# Line_trigger.net
KiCad netlist of a schematic drawn in Altium Designer
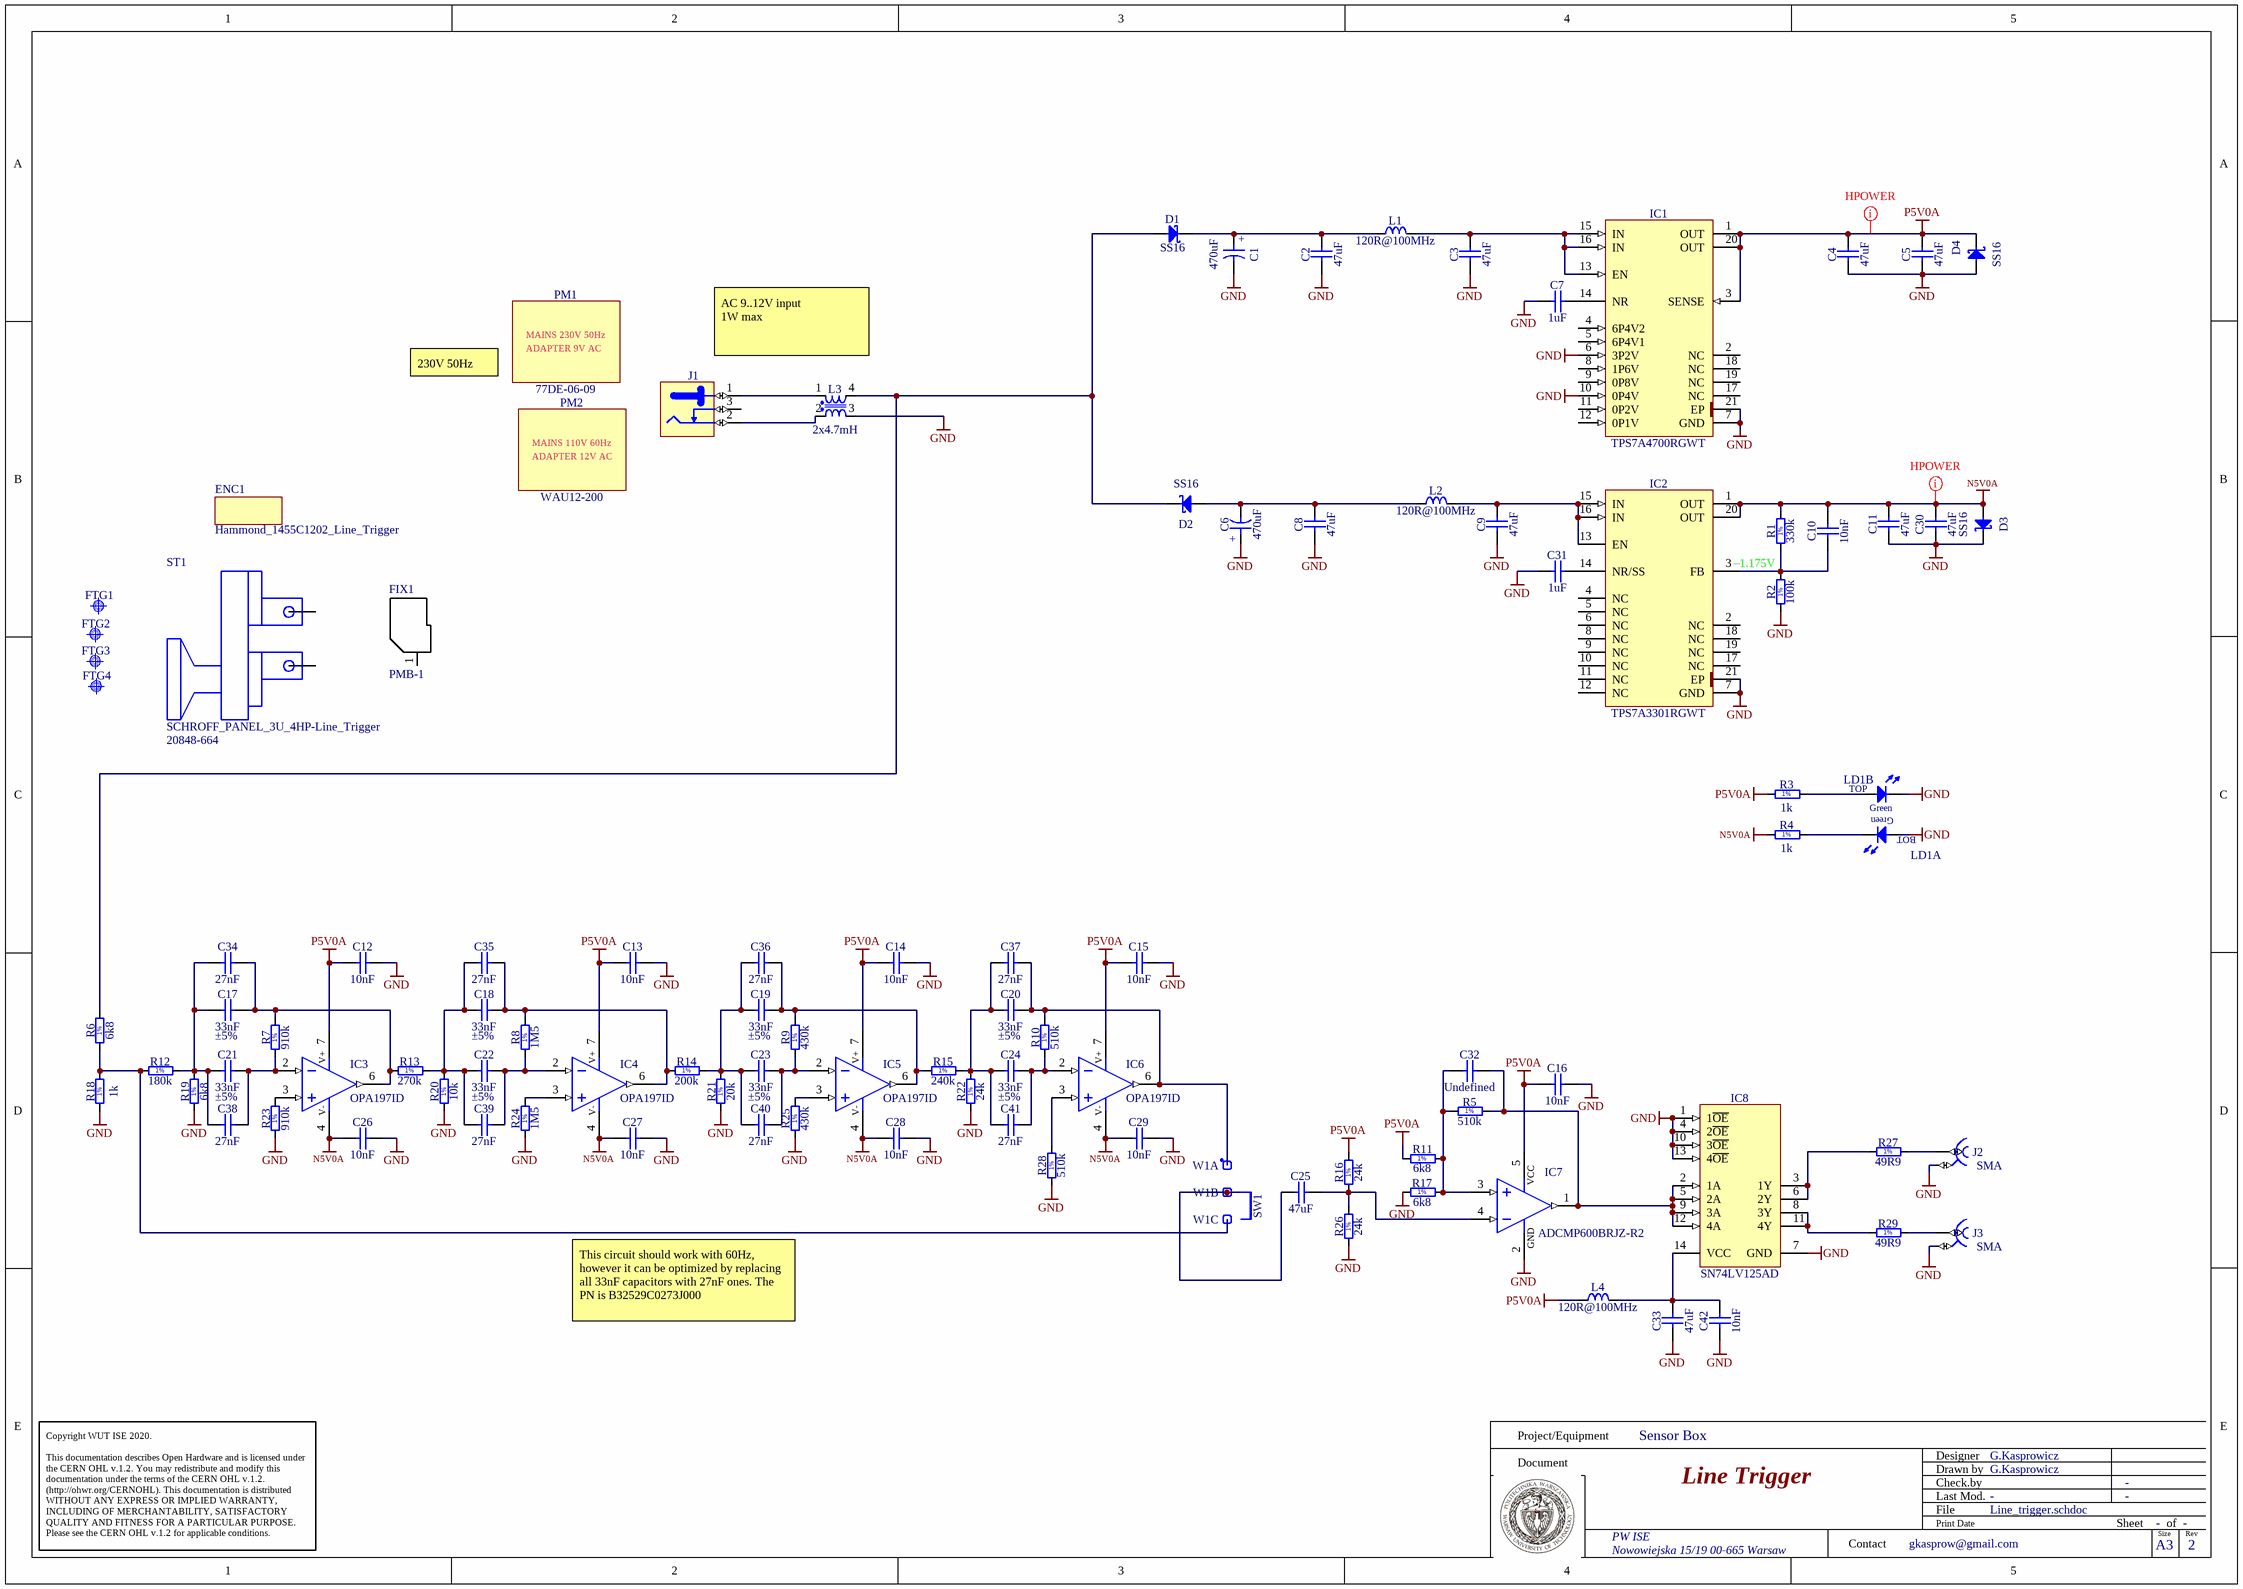
[diagram p0: Line_trigger.schdoc]

(export (version "E")
  (design (tool "Eeschema 10.0.6"))
  (components
    (comp (ref "C1")
      (value "470uF")
      (footprint "CAPAE1030X1020N")
      (description "Polarised capacitor")
      (fields (field (name "PART NUMBER") "CAE1030-1020_470UF_25V_20%") (field (name "VOLTAGE") "25V"))
      (libsource (lib "Capacitors") (part "Capacitor - polarized"))
    )
    (comp (ref "C2")
      (value "47uF")
      (footprint "CAPC3216X180N")
      (description "Non-polarised capacitor")
      (fields (field (name "PART NUMBER") "CC1206_47UF_25V_20%_X5R") (field (name "VOLTAGE") "25V"))
      (libsource (lib "Capacitors") (part "Capacitor - non polarized"))
    )
    (comp (ref "C3")
      (value "47uF")
      (footprint "CAPC3216X180N")
      (description "Non-polarised capacitor")
      (fields (field (name "PART NUMBER") "CC1206_47UF_25V_20%_X5R") (field (name "VOLTAGE") "25V"))
      (libsource (lib "Capacitors") (part "Capacitor - non polarized"))
    )
    (comp (ref "C4")
      (value "47uF")
      (footprint "CAPC3216X180N")
      (description "Non-polarised capacitor")
      (fields (field (name "PART NUMBER") "CC1206_47UF_25V_20%_X5R") (field (name "VOLTAGE") "25V"))
      (libsource (lib "Capacitors") (part "Capacitor - non polarized"))
    )
    (comp (ref "C5")
      (value "47uF")
      (footprint "CAPC3216X180N")
      (description "Non-polarised capacitor")
      (fields (field (name "PART NUMBER") "CC1206_47UF_25V_20%_X5R") (field (name "VOLTAGE") "25V"))
      (libsource (lib "Capacitors") (part "Capacitor - non polarized"))
    )
    (comp (ref "C6")
      (value "470uF")
      (footprint "CAPAE1030X1020N")
      (description "Polarised capacitor")
      (fields (field (name "PART NUMBER") "CAE1030-1020_470UF_25V_20%") (field (name "VOLTAGE") "25V"))
      (libsource (lib "Capacitors") (part "Capacitor - polarized"))
    )
    (comp (ref "C7")
      (value "1uF")
      (footprint "CAPC1608X87N")
      (description "Non-polarised capacitor")
      (fields (field (name "PART NUMBER") "CC0603_1UF_25V_10%_X7R") (field (name "VOLTAGE") "25V"))
      (libsource (lib "Capacitors") (part "Capacitor - non polarized"))
    )
    (comp (ref "C8")
      (value "47uF")
      (footprint "CAPC3216X180N")
      (description "Non-polarised capacitor")
      (fields (field (name "PART NUMBER") "CC1206_47UF_25V_20%_X5R") (field (name "VOLTAGE") "25V"))
      (libsource (lib "Capacitors") (part "Capacitor - non polarized"))
    )
    (comp (ref "C9")
      (value "47uF")
      (footprint "CAPC3216X180N")
      (description "Non-polarised capacitor")
      (fields (field (name "PART NUMBER") "CC1206_47UF_25V_20%_X5R") (field (name "VOLTAGE") "25V"))
      (libsource (lib "Capacitors") (part "Capacitor - non polarized"))
    )
    (comp (ref "C10")
      (value "10nF")
      (footprint "CAPC1608X87N")
      (description "Non-polarised capacitor")
      (fields (field (name "PART NUMBER") "CC0603_10NF_50V_10%_X7R") (field (name "VOLTAGE") "50V"))
      (libsource (lib "Capacitors") (part "Capacitor - non polarized"))
    )
    (comp (ref "C11")
      (value "47uF")
      (footprint "CAPC3216X180N")
      (description "Non-polarised capacitor")
      (fields (field (name "PART NUMBER") "CC1206_47UF_25V_20%_X5R") (field (name "VOLTAGE") "25V"))
      (libsource (lib "Capacitors") (part "Capacitor - non polarized"))
    )
    (comp (ref "C12")
      (value "10nF")
      (footprint "CAPC1608X87N")
      (description "Non-polarised capacitor")
      (fields (field (name "PART NUMBER") "CC0603_10NF_50V_10%_X7R") (field (name "VOLTAGE") "50V"))
      (libsource (lib "Capacitors") (part "Capacitor - non polarized"))
    )
    (comp (ref "C13")
      (value "10nF")
      (footprint "CAPC1608X87N")
      (description "Non-polarised capacitor")
      (fields (field (name "PART NUMBER") "CC0603_10NF_50V_10%_X7R") (field (name "VOLTAGE") "50V"))
      (libsource (lib "Capacitors") (part "Capacitor - non polarized"))
    )
    (comp (ref "C14")
      (value "10nF")
      (footprint "CAPC1608X87N")
      (description "Non-polarised capacitor")
      (fields (field (name "PART NUMBER") "CC0603_10NF_50V_10%_X7R") (field (name "VOLTAGE") "50V"))
      (libsource (lib "Capacitors") (part "Capacitor - non polarized"))
    )
    (comp (ref "C15")
      (value "10nF")
      (footprint "CAPC1608X87N")
      (description "Non-polarised capacitor")
      (fields (field (name "PART NUMBER") "CC0603_10NF_50V_10%_X7R") (field (name "VOLTAGE") "50V"))
      (libsource (lib "Capacitors") (part "Capacitor - non polarized"))
    )
    (comp (ref "C16")
      (value "10nF")
      (footprint "CAPC1608X87N")
      (description "Non-polarised capacitor")
      (fields (field (name "PART NUMBER") "CC0603_10NF_50V_10%_X7R") (field (name "VOLTAGE") "50V"))
      (libsource (lib "Capacitors") (part "Capacitor - non polarized"))
    )
    (comp (ref "C17")
      (value "33nF")
      (footprint "CAPR500-250X720X650")
      (description "Non-polarised capacitor")
      (fields
        (field (name "PART NUMBER") "CPER_33NF_63V_10%_500-250X720X650")
        (field (name "VOLTAGE") "63VDC/40VAC")
        (field (name "TOLERANCE") "±5%")
      )
      (libsource (lib "Passives_RC") (part "CAP_MKT_33n_63V"))
    )
    (comp (ref "C18")
      (value "33nF")
      (footprint "CAPR500-250X720X650")
      (description "Non-polarised capacitor")
      (fields
        (field (name "PART NUMBER") "CPER_33NF_63V_10%_500-250X720X650")
        (field (name "VOLTAGE") "63VDC/40VAC")
        (field (name "TOLERANCE") "±5%")
      )
      (libsource (lib "Passives_RC") (part "CAP_MKT_33n_63V"))
    )
    (comp (ref "C19")
      (value "33nF")
      (footprint "CAPR500-250X720X650")
      (description "Non-polarised capacitor")
      (fields
        (field (name "PART NUMBER") "CPER_33NF_63V_10%_500-250X720X650")
        (field (name "VOLTAGE") "63VDC/40VAC")
        (field (name "TOLERANCE") "±5%")
      )
      (libsource (lib "Passives_RC") (part "CAP_MKT_33n_63V"))
    )
    (comp (ref "C20")
      (value "33nF")
      (footprint "CAPR500-250X720X650")
      (description "Non-polarised capacitor")
      (fields
        (field (name "PART NUMBER") "CPER_33NF_63V_10%_500-250X720X650")
        (field (name "VOLTAGE") "63VDC/40VAC")
        (field (name "TOLERANCE") "±5%")
      )
      (libsource (lib "Passives_RC") (part "CAP_MKT_33n_63V"))
    )
    (comp (ref "C21")
      (value "33nF")
      (footprint "CAPR500-250X720X650")
      (description "Non-polarised capacitor")
      (fields
        (field (name "PART NUMBER") "CPER_33NF_63V_10%_500-250X720X650")
        (field (name "VOLTAGE") "63VDC/40VAC")
        (field (name "TOLERANCE") "±5%")
      )
      (libsource (lib "Passives_RC") (part "CAP_MKT_33n_63V"))
    )
    (comp (ref "C22")
      (value "33nF")
      (footprint "CAPR500-250X720X650")
      (description "Non-polarised capacitor")
      (fields
        (field (name "PART NUMBER") "CPER_33NF_63V_10%_500-250X720X650")
        (field (name "VOLTAGE") "63VDC/40VAC")
        (field (name "TOLERANCE") "±5%")
      )
      (libsource (lib "Passives_RC") (part "CAP_MKT_33n_63V"))
    )
    (comp (ref "C23")
      (value "33nF")
      (footprint "CAPR500-250X720X650")
      (description "Non-polarised capacitor")
      (fields
        (field (name "PART NUMBER") "CPER_33NF_63V_10%_500-250X720X650")
        (field (name "VOLTAGE") "63VDC/40VAC")
        (field (name "TOLERANCE") "±5%")
      )
      (libsource (lib "Passives_RC") (part "CAP_MKT_33n_63V"))
    )
    (comp (ref "C24")
      (value "33nF")
      (footprint "CAPR500-250X720X650")
      (description "Non-polarised capacitor")
      (fields
        (field (name "PART NUMBER") "CPER_33NF_63V_10%_500-250X720X650")
        (field (name "VOLTAGE") "63VDC/40VAC")
        (field (name "TOLERANCE") "±5%")
      )
      (libsource (lib "Passives_RC") (part "CAP_MKT_33n_63V"))
    )
    (comp (ref "C25")
      (value "47uF")
      (footprint "CAPC3216X180N")
      (description "Non-polarised capacitor")
      (fields (field (name "PART NUMBER") "CC1206_47UF_25V_20%_X5R") (field (name "VOLTAGE") "25V"))
      (libsource (lib "Capacitors") (part "Capacitor - non polarized"))
    )
    (comp (ref "C26")
      (value "10nF")
      (footprint "CAPC1608X87N")
      (description "Non-polarised capacitor")
      (fields (field (name "PART NUMBER") "CC0603_10NF_50V_10%_X7R") (field (name "VOLTAGE") "50V"))
      (libsource (lib "Capacitors") (part "Capacitor - non polarized"))
    )
    (comp (ref "C27")
      (value "10nF")
      (footprint "CAPC1608X87N")
      (description "Non-polarised capacitor")
      (fields (field (name "PART NUMBER") "CC0603_10NF_50V_10%_X7R") (field (name "VOLTAGE") "50V"))
      (libsource (lib "Capacitors") (part "Capacitor - non polarized"))
    )
    (comp (ref "C28")
      (value "10nF")
      (footprint "CAPC1608X87N")
      (description "Non-polarised capacitor")
      (fields (field (name "PART NUMBER") "CC0603_10NF_50V_10%_X7R") (field (name "VOLTAGE") "50V"))
      (libsource (lib "Capacitors") (part "Capacitor - non polarized"))
    )
    (comp (ref "C29")
      (value "10nF")
      (footprint "CAPC1608X87N")
      (description "Non-polarised capacitor")
      (fields (field (name "PART NUMBER") "CC0603_10NF_50V_10%_X7R") (field (name "VOLTAGE") "50V"))
      (libsource (lib "Capacitors") (part "Capacitor - non polarized"))
    )
    (comp (ref "C30")
      (value "47uF")
      (footprint "CAPC3216X180N")
      (description "Non-polarised capacitor")
      (fields (field (name "PART NUMBER") "CC1206_47UF_25V_20%_X5R") (field (name "VOLTAGE") "25V"))
      (libsource (lib "Capacitors") (part "Capacitor - non polarized"))
    )
    (comp (ref "C31")
      (value "1uF")
      (footprint "CAPC1608X87N")
      (description "Non-polarised capacitor")
      (fields (field (name "PART NUMBER") "CC0603_1UF_25V_10%_X7R") (field (name "VOLTAGE") "25V"))
      (libsource (lib "Capacitors") (part "Capacitor - non polarized"))
    )
    (comp (ref "C32")
      (value "Undefined")
      (footprint "CAPC1608X90N")
      (description "Non-polarised capacitor")
      (fields (field (name "PART NUMBER") "CC0603_NO-VALUE"))
      (libsource (lib "Capacitors") (part "Capacitor - non polarized"))
    )
    (comp (ref "C33")
      (value "47uF")
      (footprint "CAPC3216X180N")
      (description "Non-polarised capacitor")
      (fields (field (name "PART NUMBER") "CC1206_47UF_25V_20%_X5R") (field (name "VOLTAGE") "25V"))
      (libsource (lib "Capacitors") (part "Capacitor - non polarized"))
    )
    (comp (ref "C34")
      (value "27nF")
      (footprint "CAPR500-250X720X650")
      (description "Non-polarised capacitor")
      (fields
        (field (name "PART NUMBER") "CPER_27NF_63V_10%_500-250X720X650")
        (field (name "VOLTAGE") "63VDC/40VAC")
      )
      (libsource (lib "Passives_RC") (part "CAP_MKT_27n_63V"))
    )
    (comp (ref "C35")
      (value "27nF")
      (footprint "CAPR500-250X720X650")
      (description "Non-polarised capacitor")
      (fields
        (field (name "PART NUMBER") "CPER_27NF_63V_10%_500-250X720X650")
        (field (name "VOLTAGE") "63VDC/40VAC")
      )
      (libsource (lib "Passives_RC") (part "CAP_MKT_27n_63V"))
    )
    (comp (ref "C36")
      (value "27nF")
      (footprint "CAPR500-250X720X650")
      (description "Non-polarised capacitor")
      (fields
        (field (name "PART NUMBER") "CPER_27NF_63V_10%_500-250X720X650")
        (field (name "VOLTAGE") "63VDC/40VAC")
      )
      (libsource (lib "Passives_RC") (part "CAP_MKT_27n_63V"))
    )
    (comp (ref "C37")
      (value "27nF")
      (footprint "CAPR500-250X720X650")
      (description "Non-polarised capacitor")
      (fields
        (field (name "PART NUMBER") "CPER_27NF_63V_10%_500-250X720X650")
        (field (name "VOLTAGE") "63VDC/40VAC")
      )
      (libsource (lib "Passives_RC") (part "CAP_MKT_27n_63V"))
    )
    (comp (ref "C38")
      (value "27nF")
      (footprint "CAPR500-250X720X650")
      (description "Non-polarised capacitor")
      (fields
        (field (name "PART NUMBER") "CPER_27NF_63V_10%_500-250X720X650")
        (field (name "VOLTAGE") "63VDC/40VAC")
      )
      (libsource (lib "Passives_RC") (part "CAP_MKT_27n_63V"))
    )
    (comp (ref "C39")
      (value "27nF")
      (footprint "CAPR500-250X720X650")
      (description "Non-polarised capacitor")
      (fields
        (field (name "PART NUMBER") "CPER_27NF_63V_10%_500-250X720X650")
        (field (name "VOLTAGE") "63VDC/40VAC")
      )
      (libsource (lib "Passives_RC") (part "CAP_MKT_27n_63V"))
    )
    (comp (ref "C40")
      (value "27nF")
      (footprint "CAPR500-250X720X650")
      (description "Non-polarised capacitor")
      (fields
        (field (name "PART NUMBER") "CPER_27NF_63V_10%_500-250X720X650")
        (field (name "VOLTAGE") "63VDC/40VAC")
      )
      (libsource (lib "Passives_RC") (part "CAP_MKT_27n_63V"))
    )
    (comp (ref "C41")
      (value "27nF")
      (footprint "CAPR500-250X720X650")
      (description "Non-polarised capacitor")
      (fields
        (field (name "PART NUMBER") "CPER_27NF_63V_10%_500-250X720X650")
        (field (name "VOLTAGE") "63VDC/40VAC")
      )
      (libsource (lib "Passives_RC") (part "CAP_MKT_27n_63V"))
    )
    (comp (ref "C42")
      (value "10nF")
      (footprint "CAPC1608X87N")
      (description "Non-polarised capacitor")
      (fields (field (name "PART NUMBER") "CC0603_10NF_50V_10%_X7R") (field (name "VOLTAGE") "50V"))
      (libsource (lib "Capacitors") (part "Capacitor - non polarized"))
    )
    (comp (ref "D1")
      (value "SS16")
      (footprint "DIOM5127X229N")
      (description "Schottky Diode")
      (fields (field (name "VOLTAGE") "60V") (field (name "POWER") "1A"))
      (libsource (lib "ICs And Semiconductors") (part "Diode Schottky"))
    )
    (comp (ref "D2")
      (value "SS16")
      (footprint "DIOM5127X229N")
      (description "Schottky Diode")
      (fields (field (name "VOLTAGE") "60V") (field (name "POWER") "1A"))
      (libsource (lib "ICs And Semiconductors") (part "Diode Schottky"))
    )
    (comp (ref "D3")
      (value "SS16")
      (footprint "DIOM5127X229N")
      (description "Schottky Diode")
      (fields (field (name "VOLTAGE") "60V") (field (name "POWER") "1A"))
      (libsource (lib "ICs And Semiconductors") (part "Diode Schottky"))
    )
    (comp (ref "D4")
      (value "SS16")
      (footprint "DIOM5127X229N")
      (description "Schottky Diode")
      (fields (field (name "VOLTAGE") "60V") (field (name "POWER") "1A"))
      (libsource (lib "ICs And Semiconductors") (part "Diode Schottky"))
    )
    (comp (ref "ENC1")
      (value "Hammond_1455C1202_Line_Trigger")
      (footprint "Hammond_1455C1202_Thermostat")
      (description "Hammond_1455C1202_Line_Trigger enclosure")
      (libsource (lib "Mechanical") (part "Hammond_1455C1202_Thermostat"))
    )
    (comp (ref "FIX1")
      (value "PMB-1")
      (footprint "PMB-1")
      (description "right angle PCB fixing")
      (libsource (lib "LIBRARY_SCH") (part "MECH_PCB_FIX_RA"))
    )
    (comp (ref "FTG1")
      (value "Use only in PCB")
      (footprint "FIDUCIAL_TOP_C100-200")
      (description "Fiducial Target")
      (fields (field (name "PART NUMBER") "FIDUCIAL_TARGET_C100-200"))
      (libsource (lib "Eletro-mechanical") (part "Fiducial Target"))
    )
    (comp (ref "FTG2")
      (value "Use only in PCB")
      (footprint "FIDUCIAL_TOP_S100-200")
      (description "Fiducial Target")
      (fields (field (name "PART NUMBER") "FIDUCIAL_TARGET_S100-200"))
      (libsource (lib "Eletro-mechanical") (part "Fiducial Target"))
    )
    (comp (ref "FTG3")
      (value "Use only in PCB")
      (footprint "FIDUCIAL_TOP_S100-200")
      (description "Fiducial Target")
      (fields (field (name "PART NUMBER") "FIDUCIAL_TARGET_S100-200"))
      (libsource (lib "Eletro-mechanical") (part "Fiducial Target"))
    )
    (comp (ref "FTG4")
      (value "Use only in PCB")
      (footprint "FIDUCIAL_TOP_S100-200")
      (description "Fiducial Target")
      (fields (field (name "PART NUMBER") "FIDUCIAL_TARGET_S100-200"))
      (libsource (lib "Eletro-mechanical") (part "Fiducial Target"))
    )
    (comp (ref "IC1")
      (value "TPS7A4700RGWT")
      (footprint "QFN65P500X500X100-21N-S325")
      (description "Low Noise (3uVrms), 1A, High Voltage Low-Dropout Linear Regulator")
      (fields (field (name "MANUFACTURER") "TEXAS INSTRUMENTS"))
      (libsource (lib "ICs And Semiconductors") (part "TPS7A4700RGW"))
    )
    (comp (ref "IC2")
      (value "TPS7A3301RGWT")
      (footprint "QFN65P500X500X100-21N-S325")
      (description "-1.18V to -33V -1A, Ultra-Low Noise, High PSRR, Low-Dropout Linear Regulator")
      (fields (field (name "MANUFACTURER") "TEXAS INSTRUMENTS"))
      (libsource (lib "ICs And Semiconductors") (part "TPS7A3301RGW"))
    )
    (comp (ref "IC3")
      (value "OPA197ID")
      (footprint "SOIC127P600X175-8N")
      (description "36-V, Precision, Rail-to-Rail Input/Output, Low Offset Voltage, Operational Amplifiers")
      (fields (field (name "MANUFACTURER") "TEXAS INSTRUMENTS"))
      (libsource (lib "LIBRARY_SCH") (part "OA_OPA197"))
    )
    (comp (ref "IC4")
      (value "OPA197ID")
      (footprint "SOIC127P600X175-8N")
      (description "36-V, Precision, Rail-to-Rail Input/Output, Low Offset Voltage, Operational Amplifiers")
      (fields (field (name "MANUFACTURER") "TEXAS INSTRUMENTS"))
      (libsource (lib "LIBRARY_SCH") (part "OA_OPA197"))
    )
    (comp (ref "IC5")
      (value "OPA197ID")
      (footprint "SOIC127P600X175-8N")
      (description "36-V, Precision, Rail-to-Rail Input/Output, Low Offset Voltage, Operational Amplifiers")
      (fields (field (name "MANUFACTURER") "TEXAS INSTRUMENTS"))
      (libsource (lib "LIBRARY_SCH") (part "OA_OPA197"))
    )
    (comp (ref "IC6")
      (value "OPA197ID")
      (footprint "SOIC127P600X175-8N")
      (description "36-V, Precision, Rail-to-Rail Input/Output, Low Offset Voltage, Operational Amplifiers")
      (fields (field (name "MANUFACTURER") "TEXAS INSTRUMENTS"))
      (libsource (lib "LIBRARY_SCH") (part "OA_OPA197"))
    )
    (comp (ref "IC7")
      (value "ADCMP600BRJZ-R2")
      (footprint "SOT95P280X145-5N")
      (description "Rail-to-Rail, Very Fast, 2.5 V to 5.5 V Single-Supply TTL/CMOS Comparator")
      (fields (field (name "MANUFACTURER") "ANALOG DEVICES"))
      (libsource (lib "ICs And Semiconductors") (part "ADCMP600"))
    )
    (comp (ref "IC8")
      (value "SN74LV125AD")
      (footprint "SOIC127P600X175-14N")
      (description "Quadruple Bus Buffer with 3-State Outputs")
      (fields (field (name "MANUFACTURER") "TEXAS INSTRUMENTS"))
      (libsource (lib "ICs And Semiconductors") (part "74125"))
    )
    (comp (ref "J1")
      (value "Jack")
      (footprint "SWITCHCRAFT_722RA")
      (description "2.1 mm Center Pin, 5A, 48V, Right Angle, Through Hole, , DC Power Jack Connector")
      (fields (field (name "PART NUMBER") "SWITCHCRAFT_722RA") (field (name "MANUFACTURER") "SWITCHCRAFT"))
      (libsource (lib "Connectors") (part "SWITCHCRAFT_722RA"))
    )
    (comp (ref "J2")
      (value "SMA")
      (footprint "RF249BT0050GHDW")
      (description "50 Ohm Through Hole SMA Right Angle PCB Jack")
      (fields
        (field (name "PART NUMBER") "AdamTech_RF249BT0050GHDW")
        (field (name "MANUFACTURER") "AdamTech")
      )
      (libsource (lib "Connectors") (part "CON_SMA_RF249BT0050GHDW"))
    )
    (comp (ref "J3")
      (value "SMA")
      (footprint "RF249BT0050GHDW")
      (description "50 Ohm Through Hole SMA Right Angle PCB Jack")
      (fields
        (field (name "PART NUMBER") "AdamTech_RF249BT0050GHDW")
        (field (name "MANUFACTURER") "AdamTech")
      )
      (libsource (lib "Connectors") (part "CON_SMA_RF249BT0050GHDW"))
    )
    (comp (ref "L1")
      (value "120R@100MHz")
      (footprint "INDC1608X65N")
      (description "Inductor")
      (fields (field (name "PART NUMBER") "IND0603_MURATA_BLM18SG121TN1D") (field (name "POWER") "3A"))
      (libsource (lib "Inductors & Transformers") (part "Inductor"))
    )
    (comp (ref "L2")
      (value "120R@100MHz")
      (footprint "INDC1608X65N")
      (description "Inductor")
      (fields (field (name "PART NUMBER") "IND0603_MURATA_BLM18SG121TN1D") (field (name "POWER") "3A"))
      (libsource (lib "Inductors & Transformers") (part "Inductor"))
    )
    (comp (ref "L3")
      (value "2x4.7mH")
      (footprint "IND_WURTH_WE-SL2")
      (description "Inductor Common Mode")
      (fields (field (name "PART NUMBER") "IND_4.7MH_50%_WURTH_WE-SL2-744220") (field (name "POWER") "500mA"))
      (libsource (lib "Inductors & Transformers") (part "Inductor Common Mode 1Dot-4 2Dot-3"))
    )
    (comp (ref "L4")
      (value "120R@100MHz")
      (footprint "INDC1608X65N")
      (description "Inductor")
      (fields (field (name "PART NUMBER") "IND0603_MURATA_BLM18SG121TN1D") (field (name "POWER") "3A"))
      (libsource (lib "Inductors & Transformers") (part "Inductor"))
    )
    (comp (ref "LD1")
      (value "Green/Green")
      (footprint "LED_DIALIGHT_571-0122F")
      (description "LED x2 Green 1C2A-BOT_3C4A-TOP")
      (fields (field (name "PART NUMBER") "LED_DIALIGHT_571-0122F") (field (name "MANUFACTURER") "DIALIGHT"))
      (libsource (lib "ICs And Semiconductors") (part "LED x2 Green 1C2A-BOT_3C4A-TOP"))
    )
    (comp (ref "PM1")
      (value "77DE-06-09")
      (footprint "AC_AC_77DE-06-09")
      (description "10W 230V AC-AC  Power Adaptor")
      (fields (field (name "PART NUMBER") "AC_AC_77DE-06-09") (field (name "MANUFACTURER") "Ideal Power"))
      (libsource (lib "Regulators_SMPS") (part "AC_AC_77DE-06-09"))
    )
    (comp (ref "PM2")
      (value "WAU12-200")
      (footprint "AC_AC_WAU12-200")
      (description "4W  110V AC-AC  Power Adaptor")
      (fields (field (name "PART NUMBER") "AC_AC_WAU12-200") (field (name "MANUFACTURER") "Ideal Power"))
      (libsource (lib "Regulators_SMPS") (part "AC_AC_WAU12-200"))
    )
    (comp (ref "R1")
      (value "330k")
      (footprint "RESC1608X55N")
      (description "Resistor - 1%")
      (fields (field (name "PART NUMBER") "R0603_330K_1%_0.1W_100PPM") (field (name "POWER") "0.1W"))
      (libsource (lib "Resistors") (part "Resistor - 1%"))
    )
    (comp (ref "R2")
      (value "100k")
      (footprint "RESC1608X55N")
      (description "Resistor - 1%")
      (fields (field (name "PART NUMBER") "R0603_100K_1%_0.1W_100PPM") (field (name "POWER") "0.1W"))
      (libsource (lib "Resistors") (part "Resistor - 1%"))
    )
    (comp (ref "R3")
      (value "1k")
      (footprint "RESC1608X55N")
      (description "Resistor - 1%")
      (fields (field (name "PART NUMBER") "R0603_1K_1%_0.1W_100PPM") (field (name "POWER") "0.1W"))
      (libsource (lib "Resistors") (part "Resistor - 1%"))
    )
    (comp (ref "R4")
      (value "1k")
      (footprint "RESC1608X55N")
      (description "Resistor - 1%")
      (fields (field (name "PART NUMBER") "R0603_1K_1%_0.1W_100PPM") (field (name "POWER") "0.1W"))
      (libsource (lib "Resistors") (part "Resistor - 1%"))
    )
    (comp (ref "R5")
      (value "510k")
      (footprint "RESC1608X55N")
      (description "Resistor - 1%")
      (fields (field (name "PART NUMBER") "R0603_510K_1%_0.1W_100PPM") (field (name "POWER") "0.1W"))
      (libsource (lib "Resistors") (part "Resistor - 1%"))
    )
    (comp (ref "R6")
      (value "6k8")
      (footprint "RESC1608X55N")
      (description "Resistor - 1%")
      (fields (field (name "PART NUMBER") "R0603_6K8_1%_0.1W_100PPM") (field (name "POWER") "0.1W"))
      (libsource (lib "Resistors") (part "Resistor - 1%"))
    )
    (comp (ref "R7")
      (value "910k")
      (footprint "RESC1608X55N")
      (description "Resistor - 1%")
      (fields (field (name "PART NUMBER") "R0603_910K_1%_0.1W_100PPM") (field (name "POWER") "0.1W"))
      (libsource (lib "Resistors") (part "Resistor - 1%"))
    )
    (comp (ref "R8")
      (value "1M5")
      (footprint "RESC1608X55N")
      (description "Resistor - 1%")
      (fields (field (name "PART NUMBER") "R0603_1M5_1%_0.1W_100PPM") (field (name "POWER") "0.1W"))
      (libsource (lib "Resistors") (part "Resistor - 1%"))
    )
    (comp (ref "R9")
      (value "430k")
      (footprint "RESC1608X55N")
      (description "Resistor - 1%")
      (fields (field (name "PART NUMBER") "R0603_430K_1%_0.1W_100PPM") (field (name "POWER") "0.1W"))
      (libsource (lib "Resistors") (part "Resistor - 1%"))
    )
    (comp (ref "R10")
      (value "510k")
      (footprint "RESC1608X55N")
      (description "Resistor - 1%")
      (fields (field (name "PART NUMBER") "R0603_510K_1%_0.1W_100PPM") (field (name "POWER") "0.1W"))
      (libsource (lib "Resistors") (part "Resistor - 1%"))
    )
    (comp (ref "R11")
      (value "6k8")
      (footprint "RESC1608X55N")
      (description "Resistor - 1%")
      (fields (field (name "PART NUMBER") "R0603_6K8_1%_0.1W_100PPM") (field (name "POWER") "0.1W"))
      (libsource (lib "Resistors") (part "Resistor - 1%"))
    )
    (comp (ref "R12")
      (value "180k")
      (footprint "RESC1608X55N")
      (description "Resistor - 1%")
      (fields (field (name "PART NUMBER") "R0603_180K_1%_0.1W_100PPM") (field (name "POWER") "0.1W"))
      (libsource (lib "Resistors") (part "Resistor - 1%"))
    )
    (comp (ref "R13")
      (value "270k")
      (footprint "RESC1608X55N")
      (description "Resistor - 1%")
      (fields (field (name "PART NUMBER") "R0603_270K_1%_0.1W_100PPM") (field (name "POWER") "0.1W"))
      (libsource (lib "Resistors") (part "Resistor - 1%"))
    )
    (comp (ref "R14")
      (value "200k")
      (footprint "RESC1608X55N")
      (description "Resistor - 1%")
      (fields (field (name "PART NUMBER") "R0603_200K_1%_0.1W_100PPM") (field (name "POWER") "0.1W"))
      (libsource (lib "Resistors") (part "Resistor - 1%"))
    )
    (comp (ref "R15")
      (value "240k")
      (footprint "RESC1608X55N")
      (description "Resistor - 1%")
      (fields (field (name "PART NUMBER") "R0603_240K_1%_0.1W_100PPM") (field (name "POWER") "0.1W"))
      (libsource (lib "Resistors") (part "Resistor - 1%"))
    )
    (comp (ref "R16")
      (value "24k")
      (footprint "RESC1608X55N")
      (description "Resistor - 1%")
      (fields (field (name "PART NUMBER") "R0603_24K_1%_0.1W_100PPM") (field (name "POWER") "0.1W"))
      (libsource (lib "Resistors") (part "Resistor - 1%"))
    )
    (comp (ref "R17")
      (value "6k8")
      (footprint "RESC1608X55N")
      (description "Resistor - 1%")
      (fields (field (name "PART NUMBER") "R0603_6K8_1%_0.1W_100PPM") (field (name "POWER") "0.1W"))
      (libsource (lib "Resistors") (part "Resistor - 1%"))
    )
    (comp (ref "R18")
      (value "1k")
      (footprint "RESC1608X55N")
      (description "Resistor - 1%")
      (fields (field (name "PART NUMBER") "R0603_1K_1%_0.1W_100PPM") (field (name "POWER") "0.1W"))
      (libsource (lib "Resistors") (part "Resistor - 1%"))
    )
    (comp (ref "R19")
      (value "6k8")
      (footprint "RESC1608X55N")
      (description "Resistor - 1%")
      (fields (field (name "PART NUMBER") "R0603_6K8_1%_0.1W_100PPM") (field (name "POWER") "0.1W"))
      (libsource (lib "Resistors") (part "Resistor - 1%"))
    )
    (comp (ref "R20")
      (value "10k")
      (footprint "RESC1608X55N")
      (description "Resistor - 1%")
      (fields (field (name "PART NUMBER") "R0603_10K_1%_0.1W_100PPM") (field (name "POWER") "0.1W"))
      (libsource (lib "Resistors") (part "Resistor - 1%"))
    )
    (comp (ref "R21")
      (value "20k")
      (footprint "RESC1608X55N")
      (description "Resistor - 1%")
      (fields (field (name "PART NUMBER") "R0603_20K_1%_0.1W_100PPM") (field (name "POWER") "0.1W"))
      (libsource (lib "Resistors") (part "Resistor - 1%"))
    )
    (comp (ref "R22")
      (value "24k")
      (footprint "RESC1608X55N")
      (description "Resistor - 1%")
      (fields (field (name "PART NUMBER") "R0603_24K_1%_0.1W_100PPM") (field (name "POWER") "0.1W"))
      (libsource (lib "Resistors") (part "Resistor - 1%"))
    )
    (comp (ref "R23")
      (value "910k")
      (footprint "RESC1608X55N")
      (description "Resistor - 1%")
      (fields (field (name "PART NUMBER") "R0603_910K_1%_0.1W_100PPM") (field (name "POWER") "0.1W"))
      (libsource (lib "Resistors") (part "Resistor - 1%"))
    )
    (comp (ref "R24")
      (value "1M5")
      (footprint "RESC1608X55N")
      (description "Resistor - 1%")
      (fields (field (name "PART NUMBER") "R0603_1M5_1%_0.1W_100PPM") (field (name "POWER") "0.1W"))
      (libsource (lib "Resistors") (part "Resistor - 1%"))
    )
    (comp (ref "R25")
      (value "430k")
      (footprint "RESC1608X55N")
      (description "Resistor - 1%")
      (fields (field (name "PART NUMBER") "R0603_430K_1%_0.1W_100PPM") (field (name "POWER") "0.1W"))
      (libsource (lib "Resistors") (part "Resistor - 1%"))
    )
    (comp (ref "R26")
      (value "24k")
      (footprint "RESC1608X55N")
      (description "Resistor - 1%")
      (fields (field (name "PART NUMBER") "R0603_24K_1%_0.1W_100PPM") (field (name "POWER") "0.1W"))
      (libsource (lib "Resistors") (part "Resistor - 1%"))
    )
    (comp (ref "R27")
      (value "49R9")
      (footprint "RESC1608X55N")
      (description "Resistor - 1%")
      (fields (field (name "PART NUMBER") "R0603_49R9_1%_0.1W_100PPM") (field (name "POWER") "0.1W"))
      (libsource (lib "Resistors") (part "Resistor - 1%"))
    )
    (comp (ref "R28")
      (value "510k")
      (footprint "RESC1608X55N")
      (description "Resistor - 1%")
      (fields (field (name "PART NUMBER") "R0603_510K_1%_0.1W_100PPM") (field (name "POWER") "0.1W"))
      (libsource (lib "Resistors") (part "Resistor - 1%"))
    )
    (comp (ref "R29")
      (value "49R9")
      (footprint "RESC1608X55N")
      (description "Resistor - 1%")
      (fields (field (name "PART NUMBER") "R0603_49R9_1%_0.1W_100PPM") (field (name "POWER") "0.1W"))
      (libsource (lib "Resistors") (part "Resistor - 1%"))
    )
    (comp (ref "ST1")
      (value "SCHROFF_PANEL_3U_4HP-Line_Trigger")
      (footprint "SCHROFF_PANEL_3HP_4U - Line_Trigger")
      (description "Schroff 3HP 4U EUROCARD Panel")
      (fields
        (field (name "MANUFACTURER") "Schroff")
        (field (name "MANUFACTURER PART NUMBER") "20818-017")
        (field (name "MANUFACTURER PART NUMBER 2") "20848-664")
      )
      (libsource (lib "Mechanical") (part "SCHROFF_PANEL_3U_4HP_Line_Trigger"))
    )
    (comp (ref "SW1")
      (value "Jumper Type1")
      (footprint "STELVIO-KONTEK_3131730000400")
      (description "Jumper 1 Pin")
      (fields
        (field (name "PART NUMBER") "STELVIO-KONTEK_3131730000400")
        (field (name "MANUFACTURER") "STELVIO-KONTEK")
      )
      (libsource (lib "Connectors") (part "Jumper Type1"))
    )
    (comp (ref "W1")
      (value "Test Point")
      (footprint "COMATEL_385.0358.1.03.400")
      (description "3 Mini Wire-Wrap Contact Strip Header")
      (fields
        (field (name "PART NUMBER") "COMATEL_385.0358.1.03.400")
        (field (name "MANUFACTURER") "KONTEK COMATEL")
      )
      (libsource (lib "Connectors") (part "Wire-Wrap Contact x3"))
    )
  )
  (nets
    (net (code "1") (name "GND") (class "Default")
      (node (ref "C1") (pin "2") (pinfunction "2_2") (pintype "passive"))
      (node (ref "C11") (pin "1") (pinfunction "1_1") (pintype "passive"))
      (node (ref "C12") (pin "2") (pinfunction "2_2") (pintype "passive"))
      (node (ref "C13") (pin "2") (pinfunction "2_2") (pintype "passive"))
      (node (ref "C14") (pin "2") (pinfunction "2_2") (pintype "passive"))
      (node (ref "C15") (pin "2") (pinfunction "2_2") (pintype "passive"))
      (node (ref "C16") (pin "2") (pinfunction "2_2") (pintype "passive"))
      (node (ref "C2") (pin "1") (pinfunction "1_1") (pintype "passive"))
      (node (ref "C26") (pin "2") (pinfunction "2_2") (pintype "passive"))
      (node (ref "C27") (pin "2") (pinfunction "2_2") (pintype "passive"))
      (node (ref "C28") (pin "2") (pinfunction "2_2") (pintype "passive"))
      (node (ref "C29") (pin "2") (pinfunction "2_2") (pintype "passive"))
      (node (ref "C3") (pin "1") (pinfunction "1_1") (pintype "passive"))
      (node (ref "C30") (pin "1") (pinfunction "1_1") (pintype "passive"))
      (node (ref "C31") (pin "1") (pinfunction "1_1") (pintype "passive"))
      (node (ref "C33") (pin "1") (pinfunction "1_1") (pintype "passive"))
      (node (ref "C4") (pin "1") (pinfunction "1_1") (pintype "passive"))
      (node (ref "C42") (pin "1") (pinfunction "1_1") (pintype "passive"))
      (node (ref "C5") (pin "1") (pinfunction "1_1") (pintype "passive"))
      (node (ref "C6") (pin "1") (pinfunction "1_1") (pintype "passive"))
      (node (ref "C7") (pin "1") (pinfunction "1_1") (pintype "passive"))
      (node (ref "C8") (pin "1") (pinfunction "1_1") (pintype "passive"))
      (node (ref "C9") (pin "1") (pinfunction "1_1") (pintype "passive"))
      (node (ref "D3") (pin "1") (pinfunction "C_1") (pintype "passive"))
      (node (ref "D4") (pin "2") (pinfunction "A_2") (pintype "passive"))
      (node (ref "IC1") (pin "10") (pinfunction "0P4V_10") (pintype "input"))
      (node (ref "IC1") (pin "21") (pinfunction "EP_21") (pintype "power_in"))
      (node (ref "IC1") (pin "6") (pinfunction "3P2V_6") (pintype "input"))
      (node (ref "IC1") (pin "7") (pinfunction "GND_7") (pintype "power_in"))
      (node (ref "IC2") (pin "21") (pinfunction "EP_21") (pintype "power_in"))
      (node (ref "IC2") (pin "7") (pinfunction "GND_7") (pintype "power_in"))
      (node (ref "IC7") (pin "2") (pinfunction "GND_2") (pintype "power_in"))
      (node (ref "IC8") (pin "1") (pinfunction "1~{OE}_1") (pintype "input"))
      (node (ref "IC8") (pin "10") (pinfunction "3~{OE}_10") (pintype "input"))
      (node (ref "IC8") (pin "13") (pinfunction "4~{OE}_13") (pintype "input"))
      (node (ref "IC8") (pin "4") (pinfunction "2~{OE}_4") (pintype "input"))
      (node (ref "IC8") (pin "7") (pinfunction "GND_7") (pintype "power_in"))
      (node (ref "J2") (pin "2") (pinfunction "2_2") (pintype "bidirectional"))
      (node (ref "J3") (pin "2") (pinfunction "2_2") (pintype "bidirectional"))
      (node (ref "L3") (pin "3") (pinfunction "3_3") (pintype "passive"))
      (node (ref "LD1") (pin "2") (pinfunction "A_2") (pintype "passive"))
      (node (ref "LD1") (pin "3") (pinfunction "C_3") (pintype "passive"))
      (node (ref "R17") (pin "1") (pinfunction "1_1") (pintype "passive"))
      (node (ref "R18") (pin "1") (pinfunction "1_1") (pintype "passive"))
      (node (ref "R19") (pin "1") (pinfunction "1_1") (pintype "passive"))
      (node (ref "R2") (pin "1") (pinfunction "1_1") (pintype "passive"))
      (node (ref "R20") (pin "1") (pinfunction "1_1") (pintype "passive"))
      (node (ref "R21") (pin "1") (pinfunction "1_1") (pintype "passive"))
      (node (ref "R22") (pin "1") (pinfunction "1_1") (pintype "passive"))
      (node (ref "R23") (pin "1") (pinfunction "1_1") (pintype "passive"))
      (node (ref "R24") (pin "1") (pinfunction "1_1") (pintype "passive"))
      (node (ref "R25") (pin "1") (pinfunction "1_1") (pintype "passive"))
      (node (ref "R26") (pin "1") (pinfunction "1_1") (pintype "passive"))
      (node (ref "R28") (pin "1") (pinfunction "1_1") (pintype "passive"))
    )
    (net (code "2") (name "N5V0A") (class "Default")
      (node (ref "C10") (pin "2") (pinfunction "2_2") (pintype "passive"))
      (node (ref "C11") (pin "2") (pinfunction "2_2") (pintype "passive"))
      (node (ref "C26") (pin "1") (pinfunction "1_1") (pintype "passive"))
      (node (ref "C27") (pin "1") (pinfunction "1_1") (pintype "passive"))
      (node (ref "C28") (pin "1") (pinfunction "1_1") (pintype "passive"))
      (node (ref "C29") (pin "1") (pinfunction "1_1") (pintype "passive"))
      (node (ref "C30") (pin "2") (pinfunction "2_2") (pintype "passive"))
      (node (ref "D3") (pin "2") (pinfunction "A_2") (pintype "passive"))
      (node (ref "IC2") (pin "1") (pinfunction "OUT_1") (pintype "power_in"))
      (node (ref "IC2") (pin "20") (pinfunction "OUT_20") (pintype "power_in"))
      (node (ref "IC3") (pin "4") (pinfunction "V-_4") (pintype "power_in"))
      (node (ref "IC4") (pin "4") (pinfunction "V-_4") (pintype "power_in"))
      (node (ref "IC5") (pin "4") (pinfunction "V-_4") (pintype "power_in"))
      (node (ref "IC6") (pin "4") (pinfunction "V-_4") (pintype "power_in"))
      (node (ref "R1") (pin "2") (pinfunction "2_2") (pintype "passive"))
      (node (ref "R4") (pin "1") (pinfunction "1_1") (pintype "passive"))
    )
    (net (code "3") (name "Net-(C17-Pad1)") (class "Default")
      (node (ref "C17") (pin "1") (pinfunction "1_1") (pintype "passive"))
      (node (ref "C21") (pin "1") (pinfunction "1_1") (pintype "passive"))
      (node (ref "C34") (pin "1") (pinfunction "1_1") (pintype "passive"))
      (node (ref "C38") (pin "1") (pinfunction "1_1") (pintype "passive"))
      (node (ref "R12") (pin "2") (pinfunction "2_2") (pintype "passive"))
      (node (ref "R19") (pin "2") (pinfunction "2_2") (pintype "passive"))
    )
    (net (code "4") (name "Net-(C18-Pad1)") (class "Default")
      (node (ref "C18") (pin "1") (pinfunction "1_1") (pintype "passive"))
      (node (ref "C22") (pin "1") (pinfunction "1_1") (pintype "passive"))
      (node (ref "C35") (pin "1") (pinfunction "1_1") (pintype "passive"))
      (node (ref "C39") (pin "1") (pinfunction "1_1") (pintype "passive"))
      (node (ref "R13") (pin "2") (pinfunction "2_2") (pintype "passive"))
      (node (ref "R20") (pin "2") (pinfunction "2_2") (pintype "passive"))
    )
    (net (code "5") (name "Net-(C19-Pad1)") (class "Default")
      (node (ref "C19") (pin "1") (pinfunction "1_1") (pintype "passive"))
      (node (ref "C23") (pin "1") (pinfunction "1_1") (pintype "passive"))
      (node (ref "C36") (pin "1") (pinfunction "1_1") (pintype "passive"))
      (node (ref "C40") (pin "1") (pinfunction "1_1") (pintype "passive"))
      (node (ref "R14") (pin "2") (pinfunction "2_2") (pintype "passive"))
      (node (ref "R21") (pin "2") (pinfunction "2_2") (pintype "passive"))
    )
    (net (code "6") (name "Net-(C20-Pad1)") (class "Default")
      (node (ref "C20") (pin "1") (pinfunction "1_1") (pintype "passive"))
      (node (ref "C24") (pin "1") (pinfunction "1_1") (pintype "passive"))
      (node (ref "C37") (pin "1") (pinfunction "1_1") (pintype "passive"))
      (node (ref "C41") (pin "1") (pinfunction "1_1") (pintype "passive"))
      (node (ref "R15") (pin "2") (pinfunction "2_2") (pintype "passive"))
      (node (ref "R22") (pin "2") (pinfunction "2_2") (pintype "passive"))
    )
    (net (code "7") (name "Net-(C25-Pad1)") (class "Default")
      (node (ref "C25") (pin "1") (pinfunction "1_1") (pintype "passive"))
      (node (ref "SW1") (pin "1") (pinfunction "1_1") (pintype "bidirectional"))
      (node (ref "W1") (pin "2") (pinfunction "2_2") (pintype "bidirectional"))
    )
    (net (code "8") (name "Net-(D1-A)") (class "Default")
      (node (ref "D1") (pin "2") (pinfunction "A_2") (pintype "passive"))
      (node (ref "D2") (pin "1") (pinfunction "C_1") (pintype "passive"))
      (node (ref "L3") (pin "4") (pinfunction "4_4") (pintype "passive"))
      (node (ref "R6") (pin "2") (pinfunction "2_2") (pintype "passive"))
    )
    (net (code "9") (name "Net-(D1-C)") (class "Default")
      (node (ref "C1") (pin "1") (pinfunction "1_1") (pintype "passive"))
      (node (ref "C2") (pin "2") (pinfunction "2_2") (pintype "passive"))
      (node (ref "D1") (pin "1") (pinfunction "C_1") (pintype "passive"))
      (node (ref "L1") (pin "1") (pinfunction "1_1") (pintype "passive"))
    )
    (net (code "10") (name "Net-(D2-A)") (class "Default")
      (node (ref "C6") (pin "2") (pinfunction "2_2") (pintype "passive"))
      (node (ref "C8") (pin "2") (pinfunction "2_2") (pintype "passive"))
      (node (ref "D2") (pin "2") (pinfunction "A_2") (pintype "passive"))
      (node (ref "L2") (pin "1") (pinfunction "1_1") (pintype "passive"))
    )
    (net (code "11") (name "Net-(IC1-EN)") (class "Default")
      (node (ref "C3") (pin "2") (pinfunction "2_2") (pintype "passive"))
      (node (ref "IC1") (pin "13") (pinfunction "EN_13") (pintype "input"))
      (node (ref "IC1") (pin "15") (pinfunction "IN_15") (pintype "input"))
      (node (ref "IC1") (pin "16") (pinfunction "IN_16") (pintype "input"))
      (node (ref "L1") (pin "2") (pinfunction "2_2") (pintype "passive"))
    )
    (net (code "12") (name "Net-(IC1-NR)") (class "Default")
      (node (ref "C7") (pin "2") (pinfunction "2_2") (pintype "passive"))
      (node (ref "IC1") (pin "14") (pinfunction "NR_14") (pintype "passive"))
    )
    (net (code "13") (name "Net-(IC2-EN)") (class "Default")
      (node (ref "C9") (pin "2") (pinfunction "2_2") (pintype "passive"))
      (node (ref "IC2") (pin "13") (pinfunction "EN_13") (pintype "passive"))
      (node (ref "IC2") (pin "15") (pinfunction "IN_15") (pintype "input"))
      (node (ref "IC2") (pin "16") (pinfunction "IN_16") (pintype "input"))
      (node (ref "L2") (pin "2") (pinfunction "2_2") (pintype "passive"))
    )
    (net (code "14") (name "Net-(IC2-FB)") (class "Default")
      (node (ref "C10") (pin "1") (pinfunction "1_1") (pintype "passive"))
      (node (ref "IC2") (pin "3") (pinfunction "FB_3") (pintype "passive"))
      (node (ref "R1") (pin "1") (pinfunction "1_1") (pintype "passive"))
      (node (ref "R2") (pin "2") (pinfunction "2_2") (pintype "passive"))
    )
    (net (code "15") (name "Net-(IC2-NR{slash}SS)") (class "Default")
      (node (ref "C31") (pin "2") (pinfunction "2_2") (pintype "passive"))
      (node (ref "IC2") (pin "14") (pinfunction "NR/SS_14") (pintype "passive"))
    )
    (net (code "16") (name "Net-(IC3-IN+)") (class "Default")
      (node (ref "IC3") (pin "3") (pinfunction "IN+_3") (pintype "input"))
      (node (ref "R23") (pin "2") (pinfunction "2_2") (pintype "passive"))
    )
    (net (code "17") (name "Net-(IC3-IN-)") (class "Default")
      (node (ref "C21") (pin "2") (pinfunction "2_2") (pintype "passive"))
      (node (ref "C38") (pin "2") (pinfunction "2_2") (pintype "passive"))
      (node (ref "IC3") (pin "2") (pinfunction "IN-_2") (pintype "input"))
      (node (ref "R7") (pin "1") (pinfunction "1_1") (pintype "passive"))
    )
    (net (code "18") (name "Net-(IC3-OUT)") (class "Default")
      (node (ref "C17") (pin "2") (pinfunction "2_2") (pintype "passive"))
      (node (ref "C34") (pin "2") (pinfunction "2_2") (pintype "passive"))
      (node (ref "IC3") (pin "6") (pinfunction "OUT_6") (pintype "output"))
      (node (ref "R13") (pin "1") (pinfunction "1_1") (pintype "passive"))
      (node (ref "R7") (pin "2") (pinfunction "2_2") (pintype "passive"))
    )
    (net (code "19") (name "Net-(IC4-IN+)") (class "Default")
      (node (ref "IC4") (pin "3") (pinfunction "IN+_3") (pintype "input"))
      (node (ref "R24") (pin "2") (pinfunction "2_2") (pintype "passive"))
    )
    (net (code "20") (name "Net-(IC4-IN-)") (class "Default")
      (node (ref "C22") (pin "2") (pinfunction "2_2") (pintype "passive"))
      (node (ref "C39") (pin "2") (pinfunction "2_2") (pintype "passive"))
      (node (ref "IC4") (pin "2") (pinfunction "IN-_2") (pintype "input"))
      (node (ref "R8") (pin "1") (pinfunction "1_1") (pintype "passive"))
    )
    (net (code "21") (name "Net-(IC4-OUT)") (class "Default")
      (node (ref "C18") (pin "2") (pinfunction "2_2") (pintype "passive"))
      (node (ref "C35") (pin "2") (pinfunction "2_2") (pintype "passive"))
      (node (ref "IC4") (pin "6") (pinfunction "OUT_6") (pintype "output"))
      (node (ref "R14") (pin "1") (pinfunction "1_1") (pintype "passive"))
      (node (ref "R8") (pin "2") (pinfunction "2_2") (pintype "passive"))
    )
    (net (code "22") (name "Net-(IC5-IN+)") (class "Default")
      (node (ref "IC5") (pin "3") (pinfunction "IN+_3") (pintype "input"))
      (node (ref "R25") (pin "2") (pinfunction "2_2") (pintype "passive"))
    )
    (net (code "23") (name "Net-(IC5-IN-)") (class "Default")
      (node (ref "C23") (pin "2") (pinfunction "2_2") (pintype "passive"))
      (node (ref "C40") (pin "2") (pinfunction "2_2") (pintype "passive"))
      (node (ref "IC5") (pin "2") (pinfunction "IN-_2") (pintype "input"))
      (node (ref "R9") (pin "1") (pinfunction "1_1") (pintype "passive"))
    )
    (net (code "24") (name "Net-(IC5-OUT)") (class "Default")
      (node (ref "C19") (pin "2") (pinfunction "2_2") (pintype "passive"))
      (node (ref "C36") (pin "2") (pinfunction "2_2") (pintype "passive"))
      (node (ref "IC5") (pin "6") (pinfunction "OUT_6") (pintype "output"))
      (node (ref "R15") (pin "1") (pinfunction "1_1") (pintype "passive"))
      (node (ref "R9") (pin "2") (pinfunction "2_2") (pintype "passive"))
    )
    (net (code "25") (name "Net-(IC6-IN+)") (class "Default")
      (node (ref "IC6") (pin "3") (pinfunction "IN+_3") (pintype "input"))
      (node (ref "R28") (pin "2") (pinfunction "2_2") (pintype "passive"))
    )
    (net (code "26") (name "Net-(IC6-IN-)") (class "Default")
      (node (ref "C24") (pin "2") (pinfunction "2_2") (pintype "passive"))
      (node (ref "C41") (pin "2") (pinfunction "2_2") (pintype "passive"))
      (node (ref "IC6") (pin "2") (pinfunction "IN-_2") (pintype "input"))
      (node (ref "R10") (pin "1") (pinfunction "1_1") (pintype "passive"))
    )
    (net (code "27") (name "Net-(IC6-OUT)") (class "Default")
      (node (ref "C20") (pin "2") (pinfunction "2_2") (pintype "passive"))
      (node (ref "C37") (pin "2") (pinfunction "2_2") (pintype "passive"))
      (node (ref "IC6") (pin "6") (pinfunction "OUT_6") (pintype "output"))
      (node (ref "R10") (pin "2") (pinfunction "2_2") (pintype "passive"))
      (node (ref "W1") (pin "1") (pinfunction "1_1") (pintype "bidirectional"))
    )
    (net (code "28") (name "Net-(IC7-VN)") (class "Default")
      (node (ref "C25") (pin "2") (pinfunction "2_2") (pintype "passive"))
      (node (ref "IC7") (pin "4") (pinfunction "VN_4") (pintype "input"))
      (node (ref "R16") (pin "1") (pinfunction "1_1") (pintype "passive"))
      (node (ref "R26") (pin "2") (pinfunction "2_2") (pintype "passive"))
    )
    (net (code "29") (name "Net-(IC7-VP)") (class "Default")
      (node (ref "C32") (pin "1") (pinfunction "1_1") (pintype "passive"))
      (node (ref "IC7") (pin "3") (pinfunction "VP_3") (pintype "input"))
      (node (ref "R11") (pin "2") (pinfunction "2_2") (pintype "passive"))
      (node (ref "R17") (pin "2") (pinfunction "2_2") (pintype "passive"))
      (node (ref "R5") (pin "1") (pinfunction "1_1") (pintype "passive"))
    )
    (net (code "30") (name "Net-(IC7-q)") (class "Default")
      (node (ref "C32") (pin "2") (pinfunction "2_2") (pintype "passive"))
      (node (ref "IC7") (pin "1") (pinfunction "q_1") (pintype "output"))
      (node (ref "IC8") (pin "12") (pinfunction "4A_12") (pintype "input"))
      (node (ref "IC8") (pin "2") (pinfunction "1A_2") (pintype "input"))
      (node (ref "IC8") (pin "5") (pinfunction "2A_5") (pintype "input"))
      (node (ref "IC8") (pin "9") (pinfunction "3A_9") (pintype "input"))
      (node (ref "R5") (pin "2") (pinfunction "2_2") (pintype "passive"))
    )
    (net (code "31") (name "Net-(IC8-1Y)") (class "Default")
      (node (ref "IC8") (pin "3") (pinfunction "1Y_3") (pintype "tri_state"))
      (node (ref "IC8") (pin "6") (pinfunction "2Y_6") (pintype "tri_state"))
      (node (ref "R27") (pin "1") (pinfunction "1_1") (pintype "passive"))
    )
    (net (code "32") (name "Net-(IC8-3Y)") (class "Default")
      (node (ref "IC8") (pin "11") (pinfunction "4Y_11") (pintype "tri_state"))
      (node (ref "IC8") (pin "8") (pinfunction "3Y_8") (pintype "tri_state"))
      (node (ref "R29") (pin "1") (pinfunction "1_1") (pintype "passive"))
    )
    (net (code "33") (name "Net-(IC8-VCC)") (class "Default")
      (node (ref "C33") (pin "2") (pinfunction "2_2") (pintype "passive"))
      (node (ref "C42") (pin "2") (pinfunction "2_2") (pintype "passive"))
      (node (ref "IC8") (pin "14") (pinfunction "VCC_14") (pintype "power_in"))
      (node (ref "L4") (pin "2") (pinfunction "2_2") (pintype "passive"))
    )
    (net (code "34") (name "Net-(J1-Pad1)") (class "Default")
      (node (ref "J1") (pin "1") (pinfunction "1_1") (pintype "bidirectional"))
      (node (ref "L3") (pin "1") (pinfunction "1_1") (pintype "passive"))
    )
    (net (code "35") (name "Net-(J1-Pad2)") (class "Default")
      (node (ref "J1") (pin "2") (pinfunction "2_2") (pintype "bidirectional"))
      (node (ref "L3") (pin "2") (pinfunction "2_2") (pintype "passive"))
    )
    (net (code "36") (name "Net-(J2-Pad1)") (class "Default")
      (node (ref "J2") (pin "1") (pinfunction "1_1") (pintype "bidirectional"))
      (node (ref "R27") (pin "2") (pinfunction "2_2") (pintype "passive"))
    )
    (net (code "37") (name "Net-(J3-Pad1)") (class "Default")
      (node (ref "J3") (pin "1") (pinfunction "1_1") (pintype "bidirectional"))
      (node (ref "R29") (pin "2") (pinfunction "2_2") (pintype "passive"))
    )
    (net (code "38") (name "Net-(LD1A-C)") (class "Default")
      (node (ref "LD1") (pin "1") (pinfunction "C_1") (pintype "passive"))
      (node (ref "R4") (pin "2") (pinfunction "2_2") (pintype "passive"))
    )
    (net (code "39") (name "Net-(LD1B-A)") (class "Default")
      (node (ref "LD1") (pin "4") (pinfunction "A_4") (pintype "passive"))
      (node (ref "R3") (pin "2") (pinfunction "2_2") (pintype "passive"))
    )
    (net (code "40") (name "Net-(R12-Pad1)") (class "Default")
      (node (ref "R12") (pin "1") (pinfunction "1_1") (pintype "passive"))
      (node (ref "R18") (pin "2") (pinfunction "2_2") (pintype "passive"))
      (node (ref "R6") (pin "1") (pinfunction "1_1") (pintype "passive"))
      (node (ref "W1") (pin "3") (pinfunction "3_3") (pintype "bidirectional"))
    )
    (net (code "41") (name "P5V0A") (class "Default")
      (node (ref "C12") (pin "1") (pinfunction "1_1") (pintype "passive"))
      (node (ref "C13") (pin "1") (pinfunction "1_1") (pintype "passive"))
      (node (ref "C14") (pin "1") (pinfunction "1_1") (pintype "passive"))
      (node (ref "C15") (pin "1") (pinfunction "1_1") (pintype "passive"))
      (node (ref "C16") (pin "1") (pinfunction "1_1") (pintype "passive"))
      (node (ref "C4") (pin "2") (pinfunction "2_2") (pintype "passive"))
      (node (ref "C5") (pin "2") (pinfunction "2_2") (pintype "passive"))
      (node (ref "D4") (pin "1") (pinfunction "C_1") (pintype "passive"))
      (node (ref "IC1") (pin "1") (pinfunction "OUT_1") (pintype "power_in"))
      (node (ref "IC1") (pin "20") (pinfunction "OUT_20") (pintype "power_in"))
      (node (ref "IC1") (pin "3") (pinfunction "SENSE_3") (pintype "input"))
      (node (ref "IC3") (pin "7") (pinfunction "V+_7") (pintype "power_in"))
      (node (ref "IC4") (pin "7") (pinfunction "V+_7") (pintype "power_in"))
      (node (ref "IC5") (pin "7") (pinfunction "V+_7") (pintype "power_in"))
      (node (ref "IC6") (pin "7") (pinfunction "V+_7") (pintype "power_in"))
      (node (ref "IC7") (pin "5") (pinfunction "VCC_5") (pintype "power_in"))
      (node (ref "L4") (pin "1") (pinfunction "1_1") (pintype "passive"))
      (node (ref "R11") (pin "1") (pinfunction "1_1") (pintype "passive"))
      (node (ref "R16") (pin "2") (pinfunction "2_2") (pintype "passive"))
      (node (ref "R3") (pin "1") (pinfunction "1_1") (pintype "passive"))
    )
    (net (code "42") (name "unconnected-(FIX1-Pad1)") (class "Default")
      (node (ref "FIX1") (pin "1") (pinfunction "1_1") (pintype "passive"))
    )
    (net (code "43") (name "unconnected-(IC1-0P1V-Pad12)") (class "Default")
      (node (ref "IC1") (pin "12") (pinfunction "0P1V_12") (pintype "input"))
    )
    (net (code "44") (name "unconnected-(IC1-0P2V-Pad11)") (class "Default")
      (node (ref "IC1") (pin "11") (pinfunction "0P2V_11") (pintype "input"))
    )
    (net (code "45") (name "unconnected-(IC1-0P8V-Pad9)") (class "Default")
      (node (ref "IC1") (pin "9") (pinfunction "0P8V_9") (pintype "input"))
    )
    (net (code "46") (name "unconnected-(IC1-1P6V-Pad8)") (class "Default")
      (node (ref "IC1") (pin "8") (pinfunction "1P6V_8") (pintype "input"))
    )
    (net (code "47") (name "unconnected-(IC1-6P4V1-Pad5)") (class "Default")
      (node (ref "IC1") (pin "5") (pinfunction "6P4V1_5") (pintype "input"))
    )
    (net (code "48") (name "unconnected-(IC1-6P4V2-Pad4)") (class "Default")
      (node (ref "IC1") (pin "4") (pinfunction "6P4V2_4") (pintype "input"))
    )
    (net (code "49") (name "unconnected-(IC1-NC-Pad2)") (class "Default")
      (node (ref "IC1") (pin "2") (pinfunction "NC_2") (pintype "passive"))
    )
    (net (code "50") (name "unconnected-(IC1-NC-Pad17)") (class "Default")
      (node (ref "IC1") (pin "17") (pinfunction "NC_17") (pintype "passive"))
    )
    (net (code "51") (name "unconnected-(IC1-NC-Pad18)") (class "Default")
      (node (ref "IC1") (pin "18") (pinfunction "NC_18") (pintype "passive"))
    )
    (net (code "52") (name "unconnected-(IC1-NC-Pad19)") (class "Default")
      (node (ref "IC1") (pin "19") (pinfunction "NC_19") (pintype "passive"))
    )
    (net (code "53") (name "unconnected-(IC2-NC-Pad2)") (class "Default")
      (node (ref "IC2") (pin "2") (pinfunction "NC_2") (pintype "passive"))
    )
    (net (code "54") (name "unconnected-(IC2-NC-Pad4)") (class "Default")
      (node (ref "IC2") (pin "4") (pinfunction "NC_4") (pintype "passive"))
    )
    (net (code "55") (name "unconnected-(IC2-NC-Pad5)") (class "Default")
      (node (ref "IC2") (pin "5") (pinfunction "NC_5") (pintype "passive"))
    )
    (net (code "56") (name "unconnected-(IC2-NC-Pad6)") (class "Default")
      (node (ref "IC2") (pin "6") (pinfunction "NC_6") (pintype "passive"))
    )
    (net (code "57") (name "unconnected-(IC2-NC-Pad8)") (class "Default")
      (node (ref "IC2") (pin "8") (pinfunction "NC_8") (pintype "passive"))
    )
    (net (code "58") (name "unconnected-(IC2-NC-Pad9)") (class "Default")
      (node (ref "IC2") (pin "9") (pinfunction "NC_9") (pintype "passive"))
    )
    (net (code "59") (name "unconnected-(IC2-NC-Pad10)") (class "Default")
      (node (ref "IC2") (pin "10") (pinfunction "NC_10") (pintype "passive"))
    )
    (net (code "60") (name "unconnected-(IC2-NC-Pad11)") (class "Default")
      (node (ref "IC2") (pin "11") (pinfunction "NC_11") (pintype "passive"))
    )
    (net (code "61") (name "unconnected-(IC2-NC-Pad12)") (class "Default")
      (node (ref "IC2") (pin "12") (pinfunction "NC_12") (pintype "passive"))
    )
    (net (code "62") (name "unconnected-(IC2-NC-Pad17)") (class "Default")
      (node (ref "IC2") (pin "17") (pinfunction "NC_17") (pintype "passive"))
    )
    (net (code "63") (name "unconnected-(IC2-NC-Pad18)") (class "Default")
      (node (ref "IC2") (pin "18") (pinfunction "NC_18") (pintype "passive"))
    )
    (net (code "64") (name "unconnected-(IC2-NC-Pad19)") (class "Default")
      (node (ref "IC2") (pin "19") (pinfunction "NC_19") (pintype "passive"))
    )
    (net (code "65") (name "unconnected-(J1-Pad3)") (class "Default")
      (node (ref "J1") (pin "3") (pinfunction "3_3") (pintype "bidirectional"))
    )
    (net (code "66") (name "unconnected-(ST1-Pad0)") (class "Default")
      (node (ref "ST1") (pin "0") (pinfunction "0_0") (pintype "passive"))
    )
    (net (code "67") (name "unconnected-(ST1-Pad1)") (class "Default")
      (node (ref "ST1") (pin "1") (pinfunction "1_1") (pintype "passive"))
    )
  )
)
